# FP_Harness.net
KiCad netlist of a schematic drawn in Altium Designer
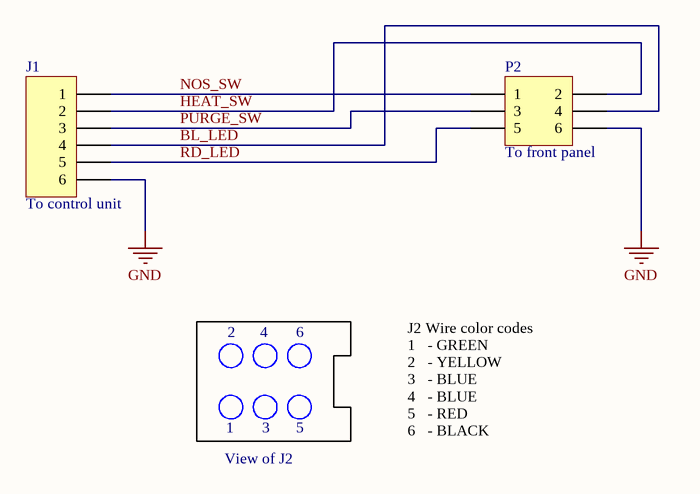
[diagram p0: FP_Harness.SchDoc]

(export (version "E")
  (design (tool "Eeschema 10.0.6"))
  (components
    (comp (ref "J1")
      (value "To control unit")
      (footprint "MOLEX_5329_6POS_RA")
      (description "Header, 6-Pin")
      (fields (field (name "PUBLISHER") "Altium Limited"))
      (libsource (lib "Miscellaneous Connectors") (part "Header 6"))
    )
    (comp (ref "P2")
      (value "To front panel")
      (footprint "HDR2X3")
      (description "Header, 3-Pin, Dual row")
      (fields (field (name "PUBLISHER") "Altium Limited"))
      (libsource (lib "Miscellaneous Connectors") (part "Header 3X2"))
    )
  )
  (nets
    (net (code "1") (name "/BL_LED") (class "Default")
      (node (ref "J1") (pin "4") (pinfunction "4_4") (pintype "passive"))
      (node (ref "P2") (pin "4") (pinfunction "4_4") (pintype "passive"))
    )
    (net (code "2") (name "/HEAT_SW") (class "Default")
      (node (ref "J1") (pin "2") (pinfunction "2_2") (pintype "passive"))
      (node (ref "P2") (pin "2") (pinfunction "2_2") (pintype "passive"))
    )
    (net (code "3") (name "/NOS_SW") (class "Default")
      (node (ref "J1") (pin "1") (pinfunction "1_1") (pintype "passive"))
      (node (ref "P2") (pin "1") (pinfunction "1_1") (pintype "passive"))
    )
    (net (code "4") (name "/PURGE_SW") (class "Default")
      (node (ref "J1") (pin "3") (pinfunction "3_3") (pintype "passive"))
      (node (ref "P2") (pin "3") (pinfunction "3_3") (pintype "passive"))
    )
    (net (code "5") (name "/RD_LED") (class "Default")
      (node (ref "J1") (pin "5") (pinfunction "5_5") (pintype "passive"))
      (node (ref "P2") (pin "5") (pinfunction "5_5") (pintype "passive"))
    )
    (net (code "6") (name "GND") (class "Default")
      (node (ref "J1") (pin "6") (pinfunction "6_6") (pintype "passive"))
      (node (ref "P2") (pin "6") (pinfunction "6_6") (pintype "passive"))
    )
  )
)
